# Sensor_board.net
KiCad netlist of a schematic drawn in EAGLE
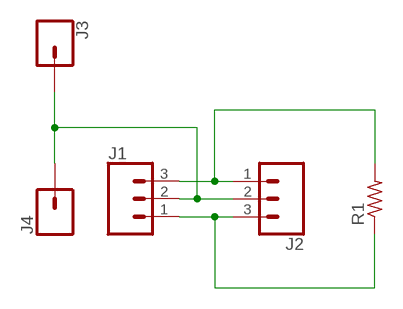
[diagram p0: schematic, sheet 1]

(export (version "E")
  (design (tool "Eeschema 10.0.6"))
  (components
    (comp (ref "J1")
      (value "CONN_03LONGPADS")
      (footprint "eagle-import:1X03_LONGPADS")
      (libsource (lib "eagle-import") (part "CONN_03LONGPADS"))
    )
    (comp (ref "J2")
      (value "CONN_03LONGPADS")
      (footprint "eagle-import:1X03_LONGPADS")
      (libsource (lib "eagle-import") (part "CONN_03LONGPADS"))
    )
    (comp (ref "J3")
      (value "CONN_01SMTSO-256-ET-0.165DIA")
      (footprint "eagle-import:SMTSO-256-ET-0.165DIA")
      (libsource (lib "eagle-import") (part "CONN_01SMTSO-256-ET-0.165DIA"))
    )
    (comp (ref "J4")
      (value "CONN_01SMTSO-256-ET-0.165DIA")
      (footprint "eagle-import:SMTSO-256-ET-0.165DIA")
      (libsource (lib "eagle-import") (part "CONN_01SMTSO-256-ET-0.165DIA"))
    )
    (comp (ref "R1")
      (value "R-US_0204/7")
      (footprint "eagle-import:0204_7")
      (libsource (lib "eagle-import") (part "R-US_0204/7"))
    )
  )
  (nets
    (net (code "1") (name "Net-(J1-Pad1)") (class "Default")
      (node (ref "J1") (pin "1") (pinfunction "1_1") (pintype "passive"))
      (node (ref "J2") (pin "3") (pinfunction "3_3") (pintype "passive"))
      (node (ref "R1") (pin "1") (pinfunction "1_1") (pintype "passive"))
    )
    (net (code "2") (name "Net-(J1-Pad3)") (class "Default")
      (node (ref "J1") (pin "3") (pinfunction "3_3") (pintype "passive"))
      (node (ref "J2") (pin "1") (pinfunction "1_1") (pintype "passive"))
      (node (ref "R1") (pin "2") (pinfunction "2_2") (pintype "passive"))
    )
    (net (code "3") (name "Net-(J3-1)") (class "Default")
      (node (ref "J1") (pin "2") (pinfunction "2_2") (pintype "passive"))
      (node (ref "J2") (pin "2") (pinfunction "2_2") (pintype "passive"))
      (node (ref "J3") (pin "P$1") (pinfunction "1_P$1") (pintype "passive"))
      (node (ref "J4") (pin "P$1") (pinfunction "1_P$1") (pintype "passive"))
    )
  )
)
